# Voltmeter.net
KiCad netlist of a schematic drawn in EAGLE
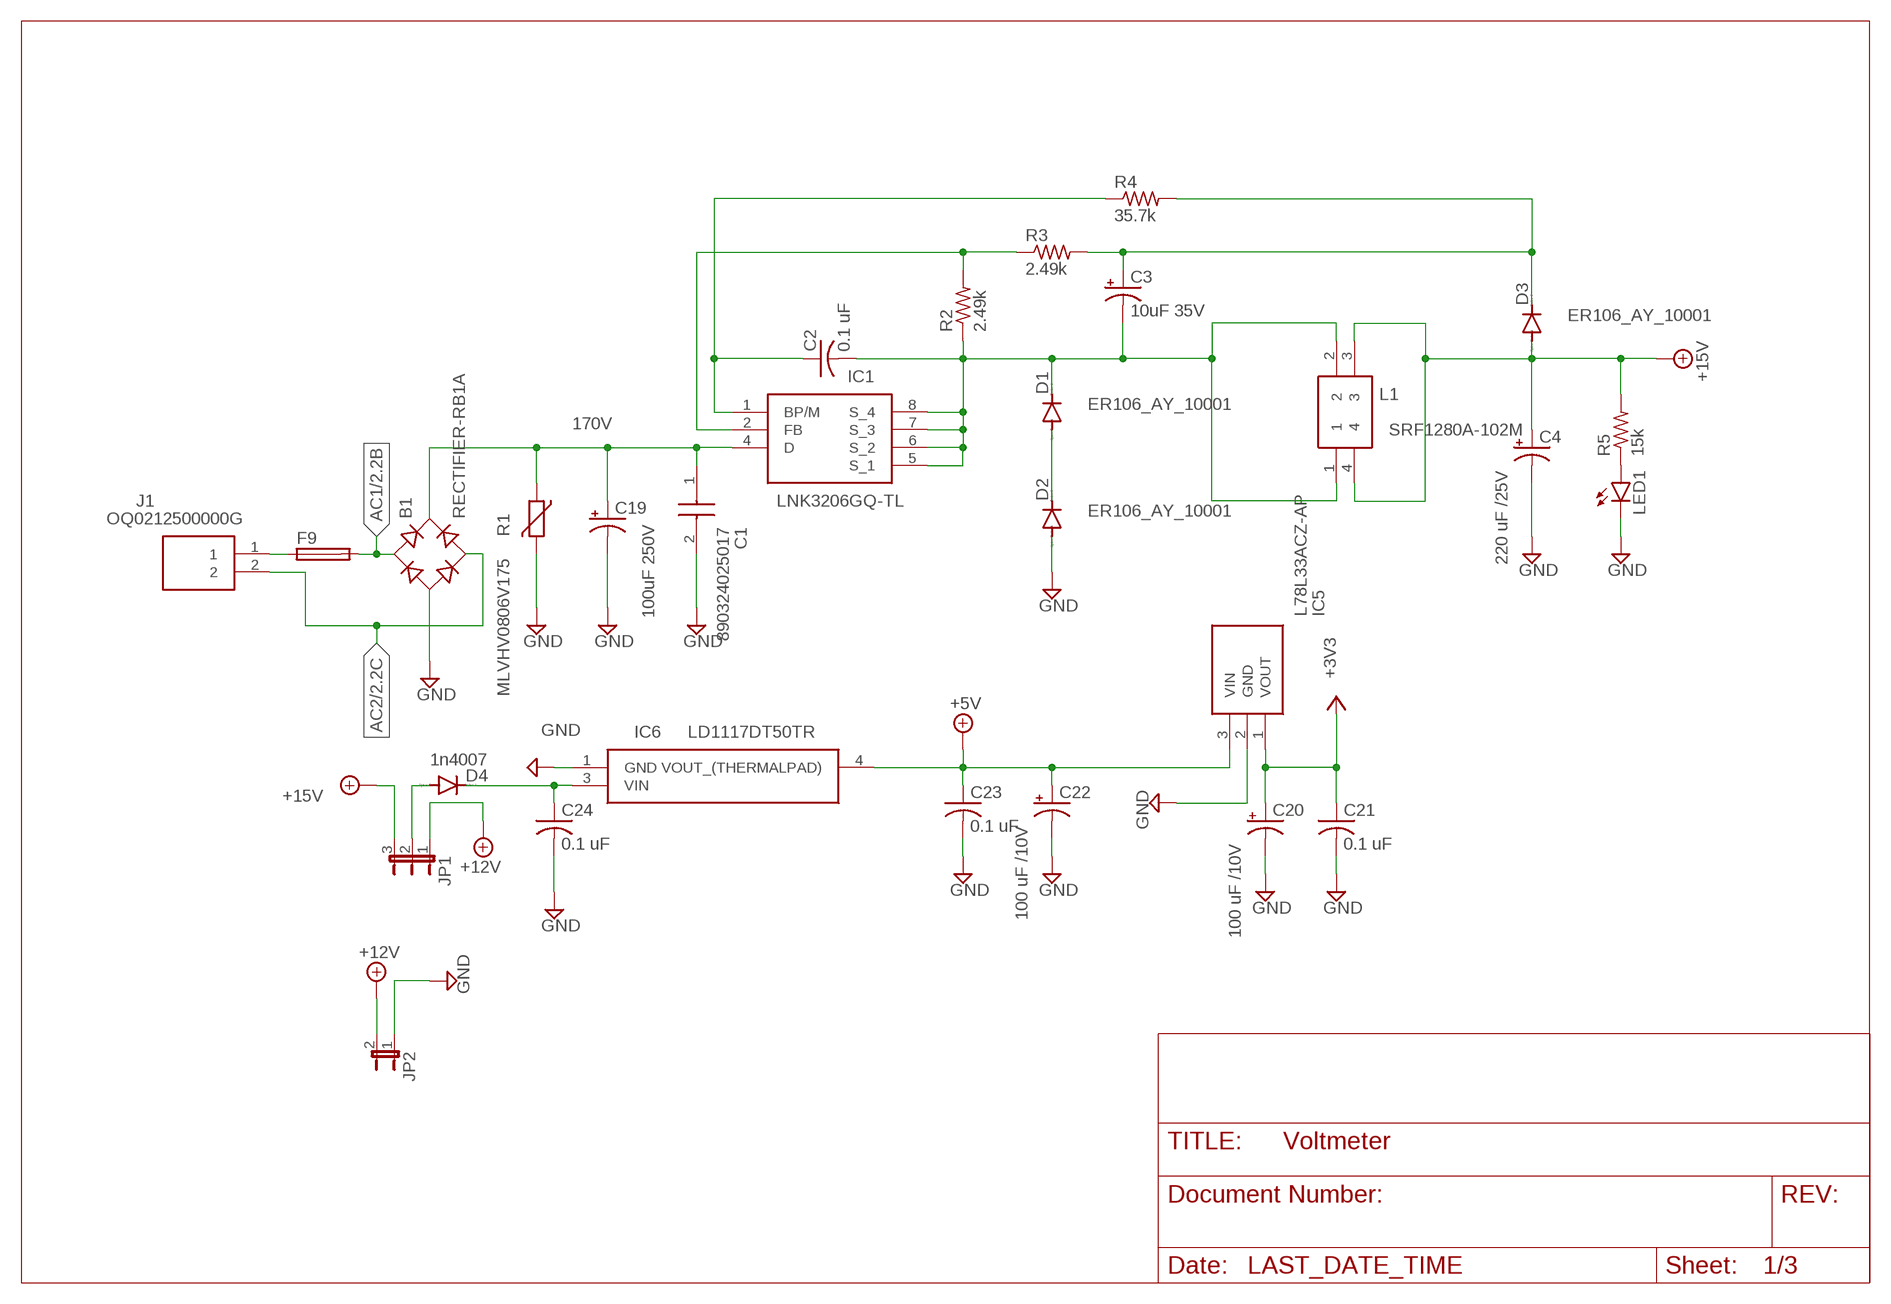
[diagram p0: schematic, sheet 1]
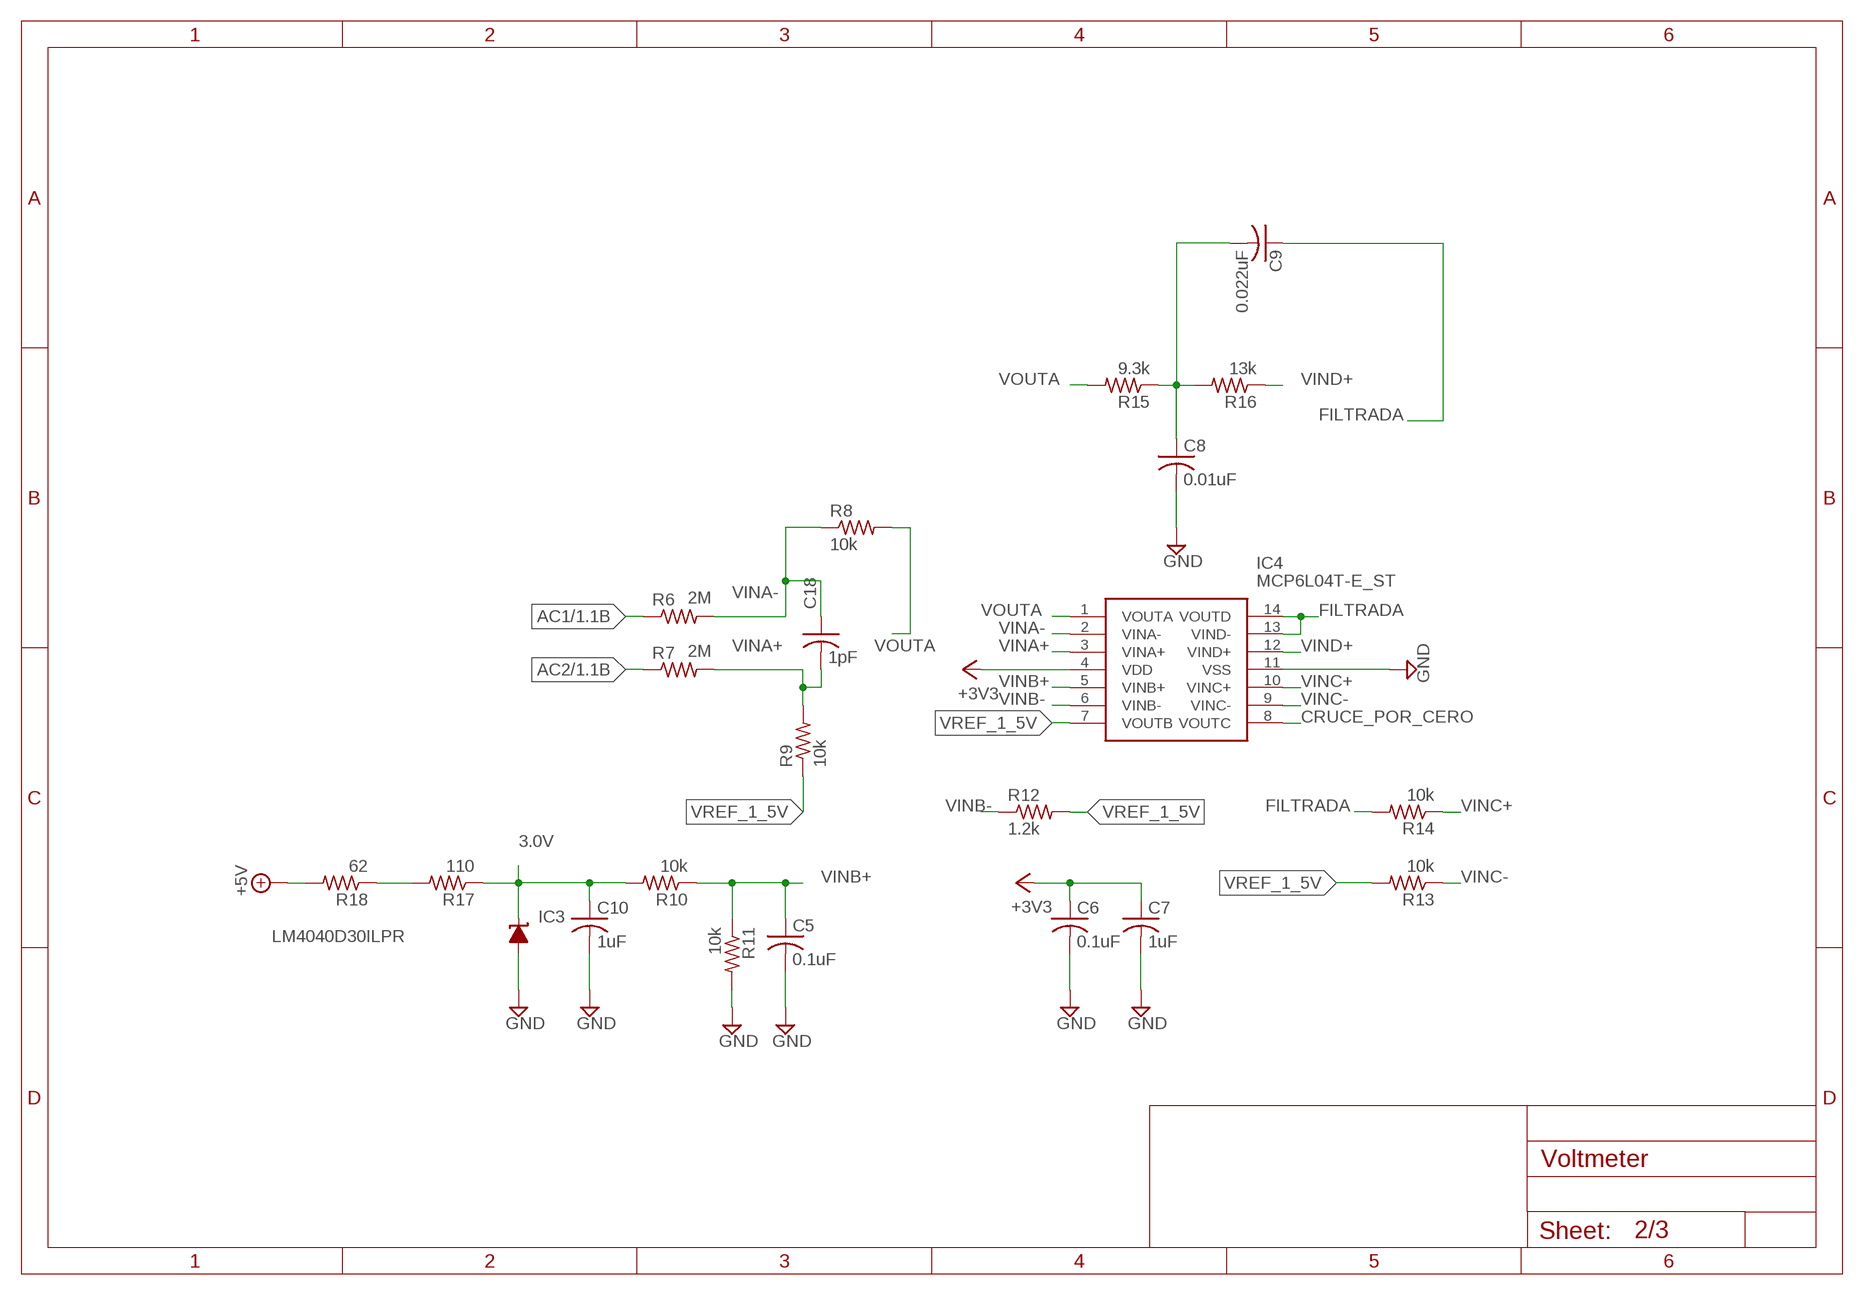
[diagram p1: schematic, sheet 2]
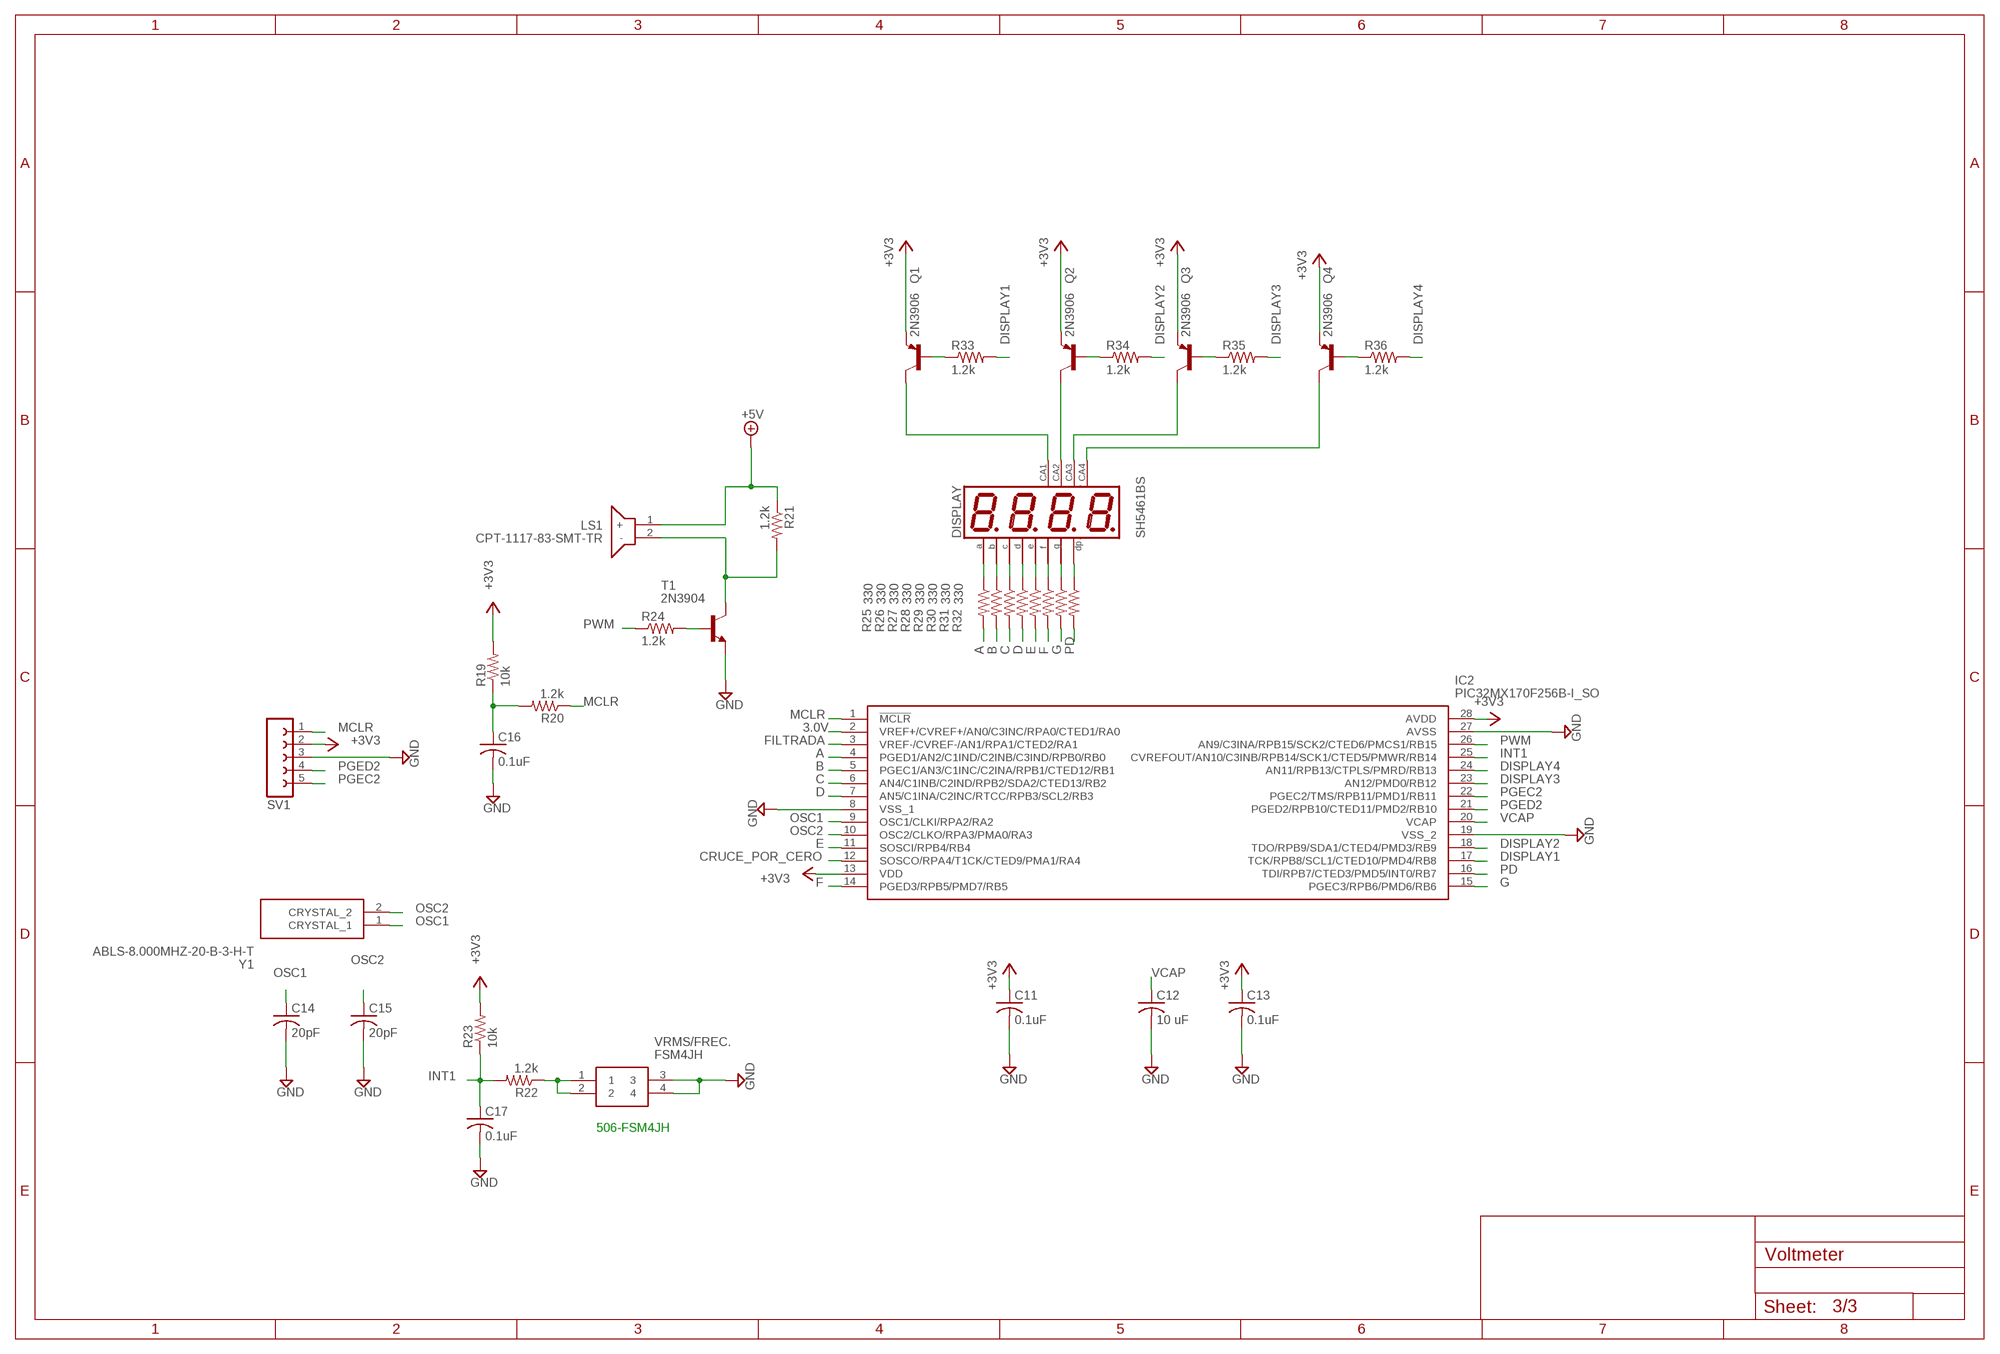
[diagram p2: schematic, sheet 3]

(export (version "E")
  (design (tool "Eeschema 10.0.6"))
  (components
    (comp (ref "C11")
      (value "0.1uF")
      (footprint "eagle-import:C0603K")
      (libsource (lib "eagle-import") (part "C-USC0603K"))
    )
    (comp (ref "C12")
      (value "10 uF")
      (footprint "eagle-import:C1206")
      (libsource (lib "eagle-import") (part "C-USC1206"))
    )
    (comp (ref "C13")
      (value "0.1uF")
      (footprint "eagle-import:C0603K")
      (libsource (lib "eagle-import") (part "C-USC0603K"))
    )
    (comp (ref "C14")
      (value "20pF")
      (footprint "eagle-import:C0603K")
      (libsource (lib "eagle-import") (part "C-USC0603K"))
    )
    (comp (ref "C15")
      (value "20pF")
      (footprint "eagle-import:C0603K")
      (libsource (lib "eagle-import") (part "C-USC0603K"))
    )
    (comp (ref "C16")
      (value "0.1uF")
      (footprint "eagle-import:C0603K")
      (libsource (lib "eagle-import") (part "C-USC0603K"))
    )
    (comp (ref "C17")
      (value "0.1uF")
      (footprint "eagle-import:C0603K")
      (libsource (lib "eagle-import") (part "C-USC0603K"))
    )
    (comp (ref "DISPLAY")
      (value "SH5461BS")
      (footprint "eagle-import:BX56_FR3")
      (libsource (lib "eagle-import") (part "SH5461BS"))
    )
    (comp (ref "IC2")
      (value "PIC32MX170F256B-I_SO")
      (footprint "eagle-import:SOIC127P1030X265-28N")
      (fields
        (field (name "MANUFACTURER_PART_NUMBER") "PIC32MX170F256B-I/SO")
        (field (name "MOUSER_PART_NUMBER") "579-32MX170F256BI/SO")
      )
      (libsource (lib "eagle-import") (part "PIC32MX170F256B-I_SO"))
    )
    (comp (ref "LS1")
      (value "CPT-1117-83-SMT-TR")
      (footprint "eagle-import:CPT111783SMTTR")
      (fields (field (name "MOUSER_PART_NUMBER") "490-CPT-1117-83SMTTR"))
      (libsource (lib "eagle-import") (part "CPT-1117-83-SMT-TR"))
    )
    (comp (ref "Q1")
      (value "2N3906")
      (footprint "eagle-import:TO92")
      (libsource (lib "eagle-import") (part "2N3906"))
    )
    (comp (ref "Q2")
      (value "2N3906")
      (footprint "eagle-import:TO92")
      (libsource (lib "eagle-import") (part "2N3906"))
    )
    (comp (ref "Q3")
      (value "2N3906")
      (footprint "eagle-import:TO92")
      (libsource (lib "eagle-import") (part "2N3906"))
    )
    (comp (ref "Q4")
      (value "2N3906")
      (footprint "eagle-import:TO92")
      (libsource (lib "eagle-import") (part "2N3906"))
    )
    (comp (ref "R19")
      (value "10k")
      (footprint "eagle-import:R0603")
      (libsource (lib "eagle-import") (part "R-US_R0603"))
    )
    (comp (ref "R20")
      (value "1.2k")
      (footprint "eagle-import:R0603")
      (libsource (lib "eagle-import") (part "R-US_R0603"))
    )
    (comp (ref "R21")
      (value "1.2k")
      (footprint "eagle-import:R0603")
      (libsource (lib "eagle-import") (part "R-US_R0603"))
    )
    (comp (ref "R22")
      (value "1.2k")
      (footprint "eagle-import:R0603")
      (libsource (lib "eagle-import") (part "R-US_R0603"))
    )
    (comp (ref "R23")
      (value "10k")
      (footprint "eagle-import:R0603")
      (libsource (lib "eagle-import") (part "R-US_R0603"))
    )
    (comp (ref "R24")
      (value "1.2k")
      (footprint "eagle-import:R0603")
      (libsource (lib "eagle-import") (part "R-US_R0603"))
    )
    (comp (ref "R25")
      (value "330")
      (footprint "eagle-import:R0603")
      (libsource (lib "eagle-import") (part "R-US_R0603"))
    )
    (comp (ref "R26")
      (value "330")
      (footprint "eagle-import:R0603")
      (libsource (lib "eagle-import") (part "R-US_R0603"))
    )
    (comp (ref "R27")
      (value "330")
      (footprint "eagle-import:R0603")
      (libsource (lib "eagle-import") (part "R-US_R0603"))
    )
    (comp (ref "R28")
      (value "330")
      (footprint "eagle-import:R0603")
      (libsource (lib "eagle-import") (part "R-US_R0603"))
    )
    (comp (ref "R29")
      (value "330")
      (footprint "eagle-import:R0603")
      (libsource (lib "eagle-import") (part "R-US_R0603"))
    )
    (comp (ref "R30")
      (value "330")
      (footprint "eagle-import:R0603")
      (libsource (lib "eagle-import") (part "R-US_R0603"))
    )
    (comp (ref "R31")
      (value "330")
      (footprint "eagle-import:R0603")
      (libsource (lib "eagle-import") (part "R-US_R0603"))
    )
    (comp (ref "R32")
      (value "330")
      (footprint "eagle-import:R0603")
      (libsource (lib "eagle-import") (part "R-US_R0603"))
    )
    (comp (ref "R33")
      (value "1.2k")
      (footprint "eagle-import:R0603")
      (libsource (lib "eagle-import") (part "R-US_R0603"))
    )
    (comp (ref "R34")
      (value "1.2k")
      (footprint "eagle-import:R0603")
      (libsource (lib "eagle-import") (part "R-US_R0603"))
    )
    (comp (ref "R35")
      (value "1.2k")
      (footprint "eagle-import:R0603")
      (libsource (lib "eagle-import") (part "R-US_R0603"))
    )
    (comp (ref "R36")
      (value "1.2k")
      (footprint "eagle-import:R0603")
      (libsource (lib "eagle-import") (part "R-US_R0603"))
    )
    (comp (ref "SV1")
      (value "FE05-1")
      (footprint "eagle-import:FE05-1")
      (libsource (lib "eagle-import") (part "FE05-1"))
    )
    (comp (ref "T1")
      (value "2N3904")
      (footprint "eagle-import:TO92")
      (libsource (lib "eagle-import") (part "2N3904"))
    )
    (comp (ref "VRMS/FREC.")
      (value "FSM4JH")
      (footprint "eagle-import:FSM4JH")
      (fields (field (name "MOUSER_PART_NUMBER") "506-FSM4JH"))
      (libsource (lib "eagle-import") (part "FSM4JH"))
    )
    (comp (ref "Y1")
      (value "ABLS-8.000MHZ-20-B-3-H-T")
      (footprint "eagle-import:ABLS8000MHZ20B3HT")
      (fields
        (field (name "MANUFACTURER_PART_NUMBER") "ABLS-8.000MHz-20-B-3-H-T")
        (field (name "MOUSER_PART_NUMBER") "815-LS8000MHZ20B3HT")
      )
      (libsource (lib "eagle-import") (part "ABLS-8.000MHZ-20-B-3-H-T"))
    )
    (comp (ref "B1")
      (value "RECTIFIER-RB1A")
      (footprint "eagle-import:RB1A")
      (libsource (lib "eagle-import") (part "RECTIFIER-RB1A"))
    )
    (comp (ref "C1")
      (value "890324025017")
      (footprint "eagle-import:890324025017")
      (fields (field (name "MOUSER_PART_NUMBER") "710-890324025017"))
      (libsource (lib "eagle-import") (part "890324025017"))
    )
    (comp (ref "C2")
      (value "0.1 uF")
      (footprint "eagle-import:C0603K")
      (libsource (lib "eagle-import") (part "C-USC0603K"))
    )
    (comp (ref "C3")
      (value "10uF 35V")
      (footprint "eagle-import:E2,5-6")
      (libsource (lib "eagle-import") (part "CPOL-USE2.5-6"))
    )
    (comp (ref "C4")
      (value "220 uF /25V")
      (footprint "eagle-import:E3,5-8")
      (libsource (lib "eagle-import") (part "CPOL-USE3.5-8"))
    )
    (comp (ref "C19")
      (value "100uF 250V")
      (footprint "eagle-import:E5-10,5")
      (libsource (lib "eagle-import") (part "CPOL-USE5-10.5"))
    )
    (comp (ref "C20")
      (value "100 uF /10V")
      (footprint "eagle-import:E2-5")
      (libsource (lib "eagle-import") (part "CPOL-USE2-5"))
    )
    (comp (ref "C21")
      (value "0.1 uF")
      (footprint "eagle-import:C0603K")
      (libsource (lib "eagle-import") (part "C-USC0603K"))
    )
    (comp (ref "C22")
      (value "100 uF /10V")
      (footprint "eagle-import:E2-5")
      (libsource (lib "eagle-import") (part "CPOL-USE2-5"))
    )
    (comp (ref "C23")
      (value "0.1 uF")
      (footprint "eagle-import:C0603K")
      (libsource (lib "eagle-import") (part "C-USC0603K"))
    )
    (comp (ref "C24")
      (value "0.1 uF")
      (footprint "eagle-import:C0603K")
      (libsource (lib "eagle-import") (part "C-USC0603K"))
    )
    (comp (ref "D1")
      (value "ER106_AY_10001")
      (footprint "eagle-import:DO41-7.6")
      (libsource (lib "eagle-import") (part "DIODE-DO41-7.6"))
    )
    (comp (ref "D2")
      (value "ER106_AY_10001")
      (footprint "eagle-import:DO41-7.6")
      (libsource (lib "eagle-import") (part "DIODE-DO41-7.6"))
    )
    (comp (ref "D3")
      (value "ER106_AY_10001")
      (footprint "eagle-import:DO41-7.6")
      (libsource (lib "eagle-import") (part "DIODE-DO41-7.6"))
    )
    (comp (ref "D4")
      (value "1n4007")
      (footprint "eagle-import:DO41-7.6")
      (libsource (lib "eagle-import") (part "DIODE-DO41-7.6"))
    )
    (comp (ref "F9")
      (value "LITTLEFUSE")
      (footprint "eagle-import:LITTLEFUSE")
      (libsource (lib "eagle-import") (part "LITTLEFUSE"))
    )
    (comp (ref "IC1")
      (value "LNK3206GQ-TL")
      (footprint "eagle-import:TOP253GNTL")
      (fields (field (name "MOUSER_PART_NUMBER") "869-LNK3206GQ-TL"))
      (libsource (lib "eagle-import") (part "LNK3206GQ-TL"))
    )
    (comp (ref "IC5")
      (value "L78L33ACZ-AP")
      (footprint "eagle-import:TS1107A1AP")
      (fields (field (name "MOUSER_PART_NUMBER") "511-L78L33ACZ-AP"))
      (libsource (lib "eagle-import") (part "L78L33ACZ-AP"))
    )
    (comp (ref "IC6")
      (value "LD1117DT50TR")
      (footprint "eagle-import:TO228P972X240-3N")
      (fields (field (name "MOUSER_PART_NUMBER") "511-LD1117DT50-TR"))
      (libsource (lib "eagle-import") (part "LD1117DT50TR"))
    )
    (comp (ref "J1")
      (value "OQ0212500000G")
      (footprint "eagle-import:OQ0212500000G")
      (fields (field (name "MOUSER_PART_NUMBER") "649-220107-C021A01LF"))
      (libsource (lib "eagle-import") (part "OQ0212500000G"))
    )
    (comp (ref "JP1")
      (value "JP2E")
      (footprint "eagle-import:JP2")
      (libsource (lib "eagle-import") (part "JP2E"))
    )
    (comp (ref "JP2")
      (value "JP1E")
      (footprint "eagle-import:JP1")
      (libsource (lib "eagle-import") (part "JP1E"))
    )
    (comp (ref "L1")
      (value "SRF1280A-102M")
      (footprint "eagle-import:SRF1280A102M")
      (fields (field (name "MOUSER_PART_NUMBER") "652-SRF1280A-102M"))
      (libsource (lib "eagle-import") (part "SRF1280A-102M"))
    )
    (comp (ref "LED1")
      (value "LEDSML0805")
      (footprint "eagle-import:SML0805")
      (libsource (lib "eagle-import") (part "LEDSML0805"))
    )
    (comp (ref "R1")
      (value "MLVHV0806V175")
      (footprint "eagle-import:CT_CN1206")
      (libsource (lib "eagle-import") (part "VARISTORCN1206"))
    )
    (comp (ref "R2")
      (value "2.49k")
      (footprint "eagle-import:R0603")
      (libsource (lib "eagle-import") (part "R-US_R0603"))
    )
    (comp (ref "R3")
      (value "2.49k")
      (footprint "eagle-import:R0603")
      (libsource (lib "eagle-import") (part "R-US_R0603"))
    )
    (comp (ref "R4")
      (value "35.7k")
      (footprint "eagle-import:R0805")
      (libsource (lib "eagle-import") (part "R-US_R0805"))
    )
    (comp (ref "R5")
      (value "15k")
      (footprint "eagle-import:R0603")
      (libsource (lib "eagle-import") (part "R-US_R0603"))
    )
    (comp (ref "C5")
      (value "0.1uF")
      (footprint "eagle-import:C0603K")
      (libsource (lib "eagle-import") (part "C-USC0603K"))
    )
    (comp (ref "C6")
      (value "0.1uF")
      (footprint "eagle-import:C0603K")
      (libsource (lib "eagle-import") (part "C-USC0603K"))
    )
    (comp (ref "C7")
      (value "1uF")
      (footprint "eagle-import:C0603K")
      (libsource (lib "eagle-import") (part "C-USC0603K"))
    )
    (comp (ref "C8")
      (value "0.01uF")
      (footprint "eagle-import:C0603K")
      (libsource (lib "eagle-import") (part "C-USC0603K"))
    )
    (comp (ref "C9")
      (value "0.022uF")
      (footprint "eagle-import:C0603K")
      (libsource (lib "eagle-import") (part "C-USC0603K"))
    )
    (comp (ref "C10")
      (value "1uF")
      (footprint "eagle-import:C0603K")
      (libsource (lib "eagle-import") (part "C-USC0603K"))
    )
    (comp (ref "C18")
      (value "1pF")
      (footprint "eagle-import:C0603K")
      (libsource (lib "eagle-import") (part "C-USC0603K"))
    )
    (comp (ref "IC3")
      (value "LM4040D30ILPR")
      (footprint "eagle-import:LP_O-PBCY-W3")
      (libsource (lib "eagle-import") (part "LM4041LPA12"))
    )
    (comp (ref "IC4")
      (value "MCP6L04T-E_ST")
      (footprint "eagle-import:SOP65P640X120-14N")
      (fields
        (field (name "MANUFACTURER_PART_NUMBER") "MCP6L04T-E/ST")
        (field (name "MOUSER_PART_NUMBER") "579-MCP6L04T-E/ST")
      )
      (libsource (lib "eagle-import") (part "MCP6L04T-E_ST"))
    )
    (comp (ref "R6")
      (value "2M")
      (footprint "eagle-import:R0603")
      (libsource (lib "eagle-import") (part "R-US_R0603"))
    )
    (comp (ref "R7")
      (value "2M")
      (footprint "eagle-import:R0603")
      (libsource (lib "eagle-import") (part "R-US_R0603"))
    )
    (comp (ref "R8")
      (value "10k")
      (footprint "eagle-import:R0603")
      (libsource (lib "eagle-import") (part "R-US_R0603"))
    )
    (comp (ref "R9")
      (value "10k")
      (footprint "eagle-import:R0603")
      (libsource (lib "eagle-import") (part "R-US_R0603"))
    )
    (comp (ref "R10")
      (value "10k")
      (footprint "eagle-import:R0603")
      (libsource (lib "eagle-import") (part "R-US_R0603"))
    )
    (comp (ref "R11")
      (value "10k")
      (footprint "eagle-import:R0603")
      (libsource (lib "eagle-import") (part "R-US_R0603"))
    )
    (comp (ref "R12")
      (value "1.2k")
      (footprint "eagle-import:R0603")
      (libsource (lib "eagle-import") (part "R-US_R0603"))
    )
    (comp (ref "R13")
      (value "10k")
      (footprint "eagle-import:R0603")
      (libsource (lib "eagle-import") (part "R-US_R0603"))
    )
    (comp (ref "R14")
      (value "10k")
      (footprint "eagle-import:R0603")
      (libsource (lib "eagle-import") (part "R-US_R0603"))
    )
    (comp (ref "R15")
      (value "9.3k")
      (footprint "eagle-import:R0603")
      (libsource (lib "eagle-import") (part "R-US_R0603"))
    )
    (comp (ref "R16")
      (value "13k")
      (footprint "eagle-import:R0603")
      (libsource (lib "eagle-import") (part "R-US_R0603"))
    )
    (comp (ref "R17")
      (value "110")
      (footprint "eagle-import:R0603")
      (libsource (lib "eagle-import") (part "R-US_R0603"))
    )
    (comp (ref "R18")
      (value "62")
      (footprint "eagle-import:R0603")
      (libsource (lib "eagle-import") (part "R-US_R0603"))
    )
  )
  (nets
    (net (code "1") (name "+3V3") (class "Default")
      (node (ref "C11") (pin "1") (pinfunction "1_1") (pintype "passive"))
      (node (ref "C13") (pin "1") (pinfunction "1_1") (pintype "passive"))
      (node (ref "C20") (pin "+") (pinfunction "+_+") (pintype "passive"))
      (node (ref "C21") (pin "1") (pinfunction "1_1") (pintype "passive"))
      (node (ref "C6") (pin "1") (pinfunction "1_1") (pintype "passive"))
      (node (ref "C7") (pin "1") (pinfunction "1_1") (pintype "passive"))
      (node (ref "IC2") (pin "13") (pinfunction "VDD_13") (pintype "bidirectional"))
      (node (ref "IC2") (pin "28") (pinfunction "AVDD_28") (pintype "bidirectional"))
      (node (ref "IC4") (pin "4") (pinfunction "VDD_4") (pintype "bidirectional"))
      (node (ref "IC5") (pin "1") (pinfunction "VOUT_1") (pintype "bidirectional"))
      (node (ref "Q1") (pin "3") (pinfunction "E_3") (pintype "passive"))
      (node (ref "Q2") (pin "3") (pinfunction "E_3") (pintype "passive"))
      (node (ref "Q3") (pin "3") (pinfunction "E_3") (pintype "passive"))
      (node (ref "Q4") (pin "3") (pinfunction "E_3") (pintype "passive"))
      (node (ref "R19") (pin "2") (pinfunction "2_2") (pintype "passive"))
      (node (ref "R23") (pin "2") (pinfunction "2_2") (pintype "passive"))
      (node (ref "SV1") (pin "2") (pinfunction "2_2") (pintype "passive"))
    )
    (net (code "2") (name "+5V") (class "Default")
      (node (ref "C22") (pin "+") (pinfunction "+_+") (pintype "passive"))
      (node (ref "C23") (pin "1") (pinfunction "1_1") (pintype "passive"))
      (node (ref "IC5") (pin "3") (pinfunction "VIN_3") (pintype "bidirectional"))
      (node (ref "IC6") (pin "4") (pinfunction "VOUT_(THERMALPAD)_4") (pintype "output"))
      (node (ref "LS1") (pin "1") (pinfunction "+_1") (pintype "bidirectional"))
      (node (ref "R18") (pin "2") (pinfunction "2_2") (pintype "passive"))
      (node (ref "R21") (pin "1") (pinfunction "1_1") (pintype "passive"))
    )
    (net (code "3") (name "+12V") (class "Default")
      (node (ref "JP1") (pin "1") (pinfunction "1_1") (pintype "passive"))
      (node (ref "JP2") (pin "2") (pinfunction "2_2") (pintype "passive"))
    )
    (net (code "4") (name "+15V") (class "Default")
      (node (ref "C4") (pin "+") (pinfunction "+_+") (pintype "passive"))
      (node (ref "D3") (pin "A") (pinfunction "A_A") (pintype "passive"))
      (node (ref "JP1") (pin "3") (pinfunction "3_3") (pintype "passive"))
      (node (ref "L1") (pin "3") (pinfunction "3_3") (pintype "bidirectional"))
      (node (ref "L1") (pin "4") (pinfunction "4_4") (pintype "bidirectional"))
      (node (ref "R5") (pin "2") (pinfunction "2_2") (pintype "passive"))
    )
    (net (code "5") (name "3.0V") (class "Default")
      (node (ref "C10") (pin "1") (pinfunction "1_1") (pintype "passive"))
      (node (ref "IC2") (pin "2") (pinfunction "VREF+/CVREF+/AN0/C3INC/RPA0/CTED1/RA0_2") (pintype "bidirectional"))
      (node (ref "IC3") (pin "2") (pinfunction "C_2") (pintype "passive"))
      (node (ref "R10") (pin "2") (pinfunction "2_2") (pintype "passive"))
      (node (ref "R17") (pin "1") (pinfunction "1_1") (pintype "passive"))
    )
    (net (code "6") (name "170V") (class "Default")
      (node (ref "B1") (pin "+") (pinfunction "+_+") (pintype "passive"))
      (node (ref "C1") (pin "1") (pinfunction "1_1") (pintype "bidirectional"))
      (node (ref "C19") (pin "+") (pinfunction "+_+") (pintype "passive"))
      (node (ref "IC1") (pin "4") (pinfunction "D_4") (pintype "bidirectional"))
      (node (ref "R1") (pin "1") (pinfunction "1_1") (pintype "passive"))
    )
    (net (code "7") (name "A") (class "Default")
      (node (ref "IC2") (pin "4") (pinfunction "PGED1/AN2/C1IND/C2INB/C3IND/RPB0/RB0_4") (pintype "bidirectional"))
      (node (ref "R25") (pin "2") (pinfunction "2_2") (pintype "passive"))
    )
    (net (code "8") (name "AC1") (class "Default")
      (node (ref "B1") (pin "AC1") (pinfunction "AC1_AC1") (pintype "passive"))
      (node (ref "F9") (pin "2") (pinfunction "2_2") (pintype "passive"))
      (node (ref "R6") (pin "1") (pinfunction "1_1") (pintype "passive"))
    )
    (net (code "9") (name "AC2") (class "Default")
      (node (ref "B1") (pin "AC2") (pinfunction "AC2_AC2") (pintype "passive"))
      (node (ref "J1") (pin "2") (pinfunction "2_2") (pintype "bidirectional"))
      (node (ref "R7") (pin "1") (pinfunction "1_1") (pintype "passive"))
    )
    (net (code "10") (name "B") (class "Default")
      (node (ref "IC2") (pin "5") (pinfunction "PGEC1/AN3/C1INC/C2INA/RPB1/CTED12/RB1_5") (pintype "bidirectional"))
      (node (ref "R26") (pin "2") (pinfunction "2_2") (pintype "passive"))
    )
    (net (code "11") (name "C") (class "Default")
      (node (ref "IC2") (pin "6") (pinfunction "AN4/C1INB/C2IND/RPB2/SDA2/CTED13/RB2_6") (pintype "bidirectional"))
      (node (ref "R27") (pin "2") (pinfunction "2_2") (pintype "passive"))
    )
    (net (code "12") (name "CRUCE_POR_CERO") (class "Default")
      (node (ref "IC2") (pin "12") (pinfunction "SOSCO/RPA4/T1CK/CTED9/PMA1/RA4_12") (pintype "bidirectional"))
      (node (ref "IC4") (pin "8") (pinfunction "VOUTC_8") (pintype "bidirectional"))
    )
    (net (code "13") (name "D") (class "Default")
      (node (ref "IC2") (pin "7") (pinfunction "AN5/C1INA/C2INC/RTCC/RPB3/SCL2/RB3_7") (pintype "bidirectional"))
      (node (ref "R28") (pin "2") (pinfunction "2_2") (pintype "passive"))
    )
    (net (code "14") (name "DISPLAY1") (class "Default")
      (node (ref "IC2") (pin "17") (pinfunction "TCK/RPB8/SCL1/CTED10/PMD4/RB8_17") (pintype "bidirectional"))
      (node (ref "R33") (pin "2") (pinfunction "2_2") (pintype "passive"))
    )
    (net (code "15") (name "DISPLAY2") (class "Default")
      (node (ref "IC2") (pin "18") (pinfunction "TDO/RPB9/SDA1/CTED4/PMD3/RB9_18") (pintype "bidirectional"))
      (node (ref "R34") (pin "2") (pinfunction "2_2") (pintype "passive"))
    )
    (net (code "16") (name "DISPLAY3") (class "Default")
      (node (ref "IC2") (pin "23") (pinfunction "AN12/PMD0/RB12_23") (pintype "bidirectional"))
      (node (ref "R35") (pin "2") (pinfunction "2_2") (pintype "passive"))
    )
    (net (code "17") (name "DISPLAY4") (class "Default")
      (node (ref "IC2") (pin "24") (pinfunction "AN11/RPB13/CTPLS/PMRD/RB13_24") (pintype "bidirectional"))
      (node (ref "R36") (pin "2") (pinfunction "2_2") (pintype "passive"))
    )
    (net (code "18") (name "E") (class "Default")
      (node (ref "IC2") (pin "11") (pinfunction "SOSCI/RPB4/RB4_11") (pintype "bidirectional"))
      (node (ref "R29") (pin "2") (pinfunction "2_2") (pintype "passive"))
    )
    (net (code "19") (name "F") (class "Default")
      (node (ref "IC2") (pin "14") (pinfunction "PGED3/RPB5/PMD7/RB5_14") (pintype "bidirectional"))
      (node (ref "R30") (pin "2") (pinfunction "2_2") (pintype "passive"))
    )
    (net (code "20") (name "FILTRADA") (class "Default")
      (node (ref "C9") (pin "1") (pinfunction "1_1") (pintype "passive"))
      (node (ref "IC2") (pin "3") (pinfunction "VREF-/CVREF-/AN1/RPA1/CTED2/RA1_3") (pintype "bidirectional"))
      (node (ref "IC4") (pin "13") (pinfunction "VIND-_13") (pintype "bidirectional"))
      (node (ref "IC4") (pin "14") (pinfunction "VOUTD_14") (pintype "bidirectional"))
      (node (ref "R14") (pin "2") (pinfunction "2_2") (pintype "passive"))
    )
    (net (code "21") (name "G") (class "Default")
      (node (ref "IC2") (pin "15") (pinfunction "PGEC3/RPB6/PMD6/RB6_15") (pintype "bidirectional"))
      (node (ref "R31") (pin "2") (pinfunction "2_2") (pintype "passive"))
    )
    (net (code "22") (name "GND") (class "Default")
      (node (ref "B1") (pin "-") (pinfunction "-_-") (pintype "passive"))
      (node (ref "C1") (pin "2") (pinfunction "2_2") (pintype "bidirectional"))
      (node (ref "C10") (pin "2") (pinfunction "2_2") (pintype "passive"))
      (node (ref "C11") (pin "2") (pinfunction "2_2") (pintype "passive"))
      (node (ref "C12") (pin "2") (pinfunction "2_2") (pintype "passive"))
      (node (ref "C13") (pin "2") (pinfunction "2_2") (pintype "passive"))
      (node (ref "C14") (pin "2") (pinfunction "2_2") (pintype "passive"))
      (node (ref "C15") (pin "2") (pinfunction "2_2") (pintype "passive"))
      (node (ref "C16") (pin "2") (pinfunction "2_2") (pintype "passive"))
      (node (ref "C17") (pin "2") (pinfunction "2_2") (pintype "passive"))
      (node (ref "C19") (pin "-") (pinfunction "-_-") (pintype "passive"))
      (node (ref "C20") (pin "-") (pinfunction "-_-") (pintype "passive"))
      (node (ref "C21") (pin "2") (pinfunction "2_2") (pintype "passive"))
      (node (ref "C22") (pin "-") (pinfunction "-_-") (pintype "passive"))
      (node (ref "C23") (pin "2") (pinfunction "2_2") (pintype "passive"))
      (node (ref "C24") (pin "2") (pinfunction "2_2") (pintype "passive"))
      (node (ref "C4") (pin "-") (pinfunction "-_-") (pintype "passive"))
      (node (ref "C5") (pin "2") (pinfunction "2_2") (pintype "passive"))
      (node (ref "C6") (pin "2") (pinfunction "2_2") (pintype "passive"))
      (node (ref "C7") (pin "2") (pinfunction "2_2") (pintype "passive"))
      (node (ref "C8") (pin "2") (pinfunction "2_2") (pintype "passive"))
      (node (ref "D2") (pin "A") (pinfunction "A_A") (pintype "passive"))
      (node (ref "IC2") (pin "19") (pinfunction "VSS_2_19") (pintype "bidirectional"))
      (node (ref "IC2") (pin "27") (pinfunction "AVSS_27") (pintype "bidirectional"))
      (node (ref "IC2") (pin "8") (pinfunction "VSS_1_8") (pintype "bidirectional"))
      (node (ref "IC3") (pin "3") (pinfunction "A_3") (pintype "passive"))
      (node (ref "IC4") (pin "11") (pinfunction "VSS_11") (pintype "bidirectional"))
      (node (ref "IC5") (pin "2") (pinfunction "GND_2") (pintype "bidirectional"))
      (node (ref "IC6") (pin "1") (pinfunction "GND_1") (pintype "input"))
      (node (ref "JP2") (pin "1") (pinfunction "1_1") (pintype "passive"))
      (node (ref "LED1") (pin "C") (pinfunction "C_C") (pintype "passive"))
      (node (ref "R1") (pin "2") (pinfunction "2_2") (pintype "passive"))
      (node (ref "R11") (pin "2") (pinfunction "2_2") (pintype "passive"))
      (node (ref "SV1") (pin "3") (pinfunction "3_3") (pintype "passive"))
      (node (ref "T1") (pin "3") (pinfunction "E_3") (pintype "passive"))
      (node (ref "VRMS/FREC.") (pin "3") (pinfunction "3_3") (pintype "bidirectional"))
      (node (ref "VRMS/FREC.") (pin "4") (pinfunction "4_4") (pintype "bidirectional"))
    )
    (net (code "23") (name "INT1") (class "Default")
      (node (ref "C17") (pin "1") (pinfunction "1_1") (pintype "passive"))
      (node (ref "IC2") (pin "25") (pinfunction "CVREFOUT/AN10/C3INB/RPB14/SCK1/CTED5/PMWR/RB14_25") (pintype "bidirectional"))
      (node (ref "R22") (pin "2") (pinfunction "2_2") (pintype "passive"))
      (node (ref "R23") (pin "1") (pinfunction "1_1") (pintype "passive"))
    )
    (net (code "24") (name "MCLR") (class "Default")
      (node (ref "IC2") (pin "1") (pinfunction "~{MCLR}_1") (pintype "bidirectional"))
      (node (ref "R20") (pin "1") (pinfunction "1_1") (pintype "passive"))
      (node (ref "SV1") (pin "1") (pinfunction "1_1") (pintype "passive"))
    )
    (net (code "25") (name "Net-(C3-Pad+)") (class "Default")
      (node (ref "C3") (pin "+") (pinfunction "+_+") (pintype "passive"))
      (node (ref "D3") (pin "C") (pinfunction "C_C") (pintype "passive"))
      (node (ref "R3") (pin "2") (pinfunction "2_2") (pintype "passive"))
      (node (ref "R4") (pin "2") (pinfunction "2_2") (pintype "passive"))
    )
    (net (code "26") (name "Net-(C8-Pad1)") (class "Default")
      (node (ref "C8") (pin "1") (pinfunction "1_1") (pintype "passive"))
      (node (ref "C9") (pin "2") (pinfunction "2_2") (pintype "passive"))
      (node (ref "R15") (pin "1") (pinfunction "1_1") (pintype "passive"))
      (node (ref "R16") (pin "2") (pinfunction "2_2") (pintype "passive"))
    )
    (net (code "27") (name "Net-(C16-Pad1)") (class "Default")
      (node (ref "C16") (pin "1") (pinfunction "1_1") (pintype "passive"))
      (node (ref "R19") (pin "1") (pinfunction "1_1") (pintype "passive"))
      (node (ref "R20") (pin "2") (pinfunction "2_2") (pintype "passive"))
    )
    (net (code "28") (name "Net-(D1-PadA)") (class "Default")
      (node (ref "D1") (pin "A") (pinfunction "A_A") (pintype "passive"))
      (node (ref "D2") (pin "C") (pinfunction "C_C") (pintype "passive"))
    )
    (net (code "29") (name "Net-(D4-PadA)") (class "Default")
      (node (ref "D4") (pin "A") (pinfunction "A_A") (pintype "passive"))
      (node (ref "JP1") (pin "2") (pinfunction "2_2") (pintype "passive"))
    )
    (net (code "30") (name "Net-(DISPLAY-A)") (class "Default")
      (node (ref "DISPLAY") (pin "11") (pinfunction "A_11") (pintype "passive"))
      (node (ref "R25") (pin "1") (pinfunction "1_1") (pintype "passive"))
    )
    (net (code "31") (name "Net-(DISPLAY-B)") (class "Default")
      (node (ref "DISPLAY") (pin "7") (pinfunction "B_7") (pintype "passive"))
      (node (ref "R26") (pin "1") (pinfunction "1_1") (pintype "passive"))
    )
    (net (code "32") (name "Net-(DISPLAY-C)") (class "Default")
      (node (ref "DISPLAY") (pin "4") (pinfunction "C_4") (pintype "passive"))
      (node (ref "R27") (pin "1") (pinfunction "1_1") (pintype "passive"))
    )
    (net (code "33") (name "Net-(DISPLAY-D)") (class "Default")
      (node (ref "DISPLAY") (pin "2") (pinfunction "D_2") (pintype "passive"))
      (node (ref "R28") (pin "1") (pinfunction "1_1") (pintype "passive"))
    )
    (net (code "34") (name "Net-(DISPLAY-DP)") (class "Default")
      (node (ref "DISPLAY") (pin "3") (pinfunction "DP_3") (pintype "passive"))
      (node (ref "R32") (pin "1") (pinfunction "1_1") (pintype "passive"))
    )
    (net (code "35") (name "Net-(DISPLAY-E)") (class "Default")
      (node (ref "DISPLAY") (pin "1") (pinfunction "E_1") (pintype "passive"))
      (node (ref "R29") (pin "1") (pinfunction "1_1") (pintype "passive"))
    )
    (net (code "36") (name "Net-(DISPLAY-F)") (class "Default")
      (node (ref "DISPLAY") (pin "10") (pinfunction "F_10") (pintype "passive"))
      (node (ref "R30") (pin "1") (pinfunction "1_1") (pintype "passive"))
    )
    (net (code "37") (name "Net-(DISPLAY-G)") (class "Default")
      (node (ref "DISPLAY") (pin "5") (pinfunction "G_5") (pintype "passive"))
      (node (ref "R31") (pin "1") (pinfunction "1_1") (pintype "passive"))
    )
    (net (code "38") (name "Net-(F9-Pad1)") (class "Default")
      (node (ref "F9") (pin "1") (pinfunction "1_1") (pintype "passive"))
      (node (ref "J1") (pin "1") (pinfunction "1_1") (pintype "bidirectional"))
    )
    (net (code "39") (name "Net-(IC1-BP{slash}M)") (class "Default")
      (node (ref "C2") (pin "1") (pinfunction "1_1") (pintype "passive"))
      (node (ref "IC1") (pin "1") (pinfunction "BP/M_1") (pintype "bidirectional"))
      (node (ref "R4") (pin "1") (pinfunction "1_1") (pintype "passive"))
    )
    (net (code "40") (name "Net-(IC1-FB)") (class "Default")
      (node (ref "IC1") (pin "2") (pinfunction "FB_2") (pintype "bidirectional"))
      (node (ref "R2") (pin "2") (pinfunction "2_2") (pintype "passive"))
      (node (ref "R3") (pin "1") (pinfunction "1_1") (pintype "passive"))
    )
    (net (code "41") (name "Net-(IC1-S_1)") (class "Default")
      (node (ref "C2") (pin "2") (pinfunction "2_2") (pintype "passive"))
      (node (ref "C3") (pin "-") (pinfunction "-_-") (pintype "passive"))
      (node (ref "D1") (pin "C") (pinfunction "C_C") (pintype "passive"))
      (node (ref "IC1") (pin "5") (pinfunction "S_1_5") (pintype "bidirectional"))
      (node (ref "IC1") (pin "6") (pinfunction "S_2_6") (pintype "bidirectional"))
      (node (ref "IC1") (pin "7") (pinfunction "S_3_7") (pintype "bidirectional"))
      (node (ref "IC1") (pin "8") (pinfunction "S_4_8") (pintype "bidirectional"))
      (node (ref "L1") (pin "1") (pinfunction "1_1") (pintype "bidirectional"))
      (node (ref "L1") (pin "2") (pinfunction "2_2") (pintype "bidirectional"))
      (node (ref "R2") (pin "1") (pinfunction "1_1") (pintype "passive"))
    )
    (net (code "42") (name "Net-(IC6-VIN)") (class "Default")
      (node (ref "C24") (pin "1") (pinfunction "1_1") (pintype "passive"))
      (node (ref "D4") (pin "C") (pinfunction "C_C") (pintype "passive"))
      (node (ref "IC6") (pin "3") (pinfunction "VIN_3") (pintype "output"))
    )
    (net (code "43") (name "Net-(LED1-PadA)") (class "Default")
      (node (ref "LED1") (pin "A") (pinfunction "A_A") (pintype "passive"))
      (node (ref "R5") (pin "1") (pinfunction "1_1") (pintype "passive"))
    )
    (net (code "44") (name "Net-(LS1--)") (class "Default")
      (node (ref "LS1") (pin "2") (pinfunction "-_2") (pintype "bidirectional"))
      (node (ref "R21") (pin "2") (pinfunction "2_2") (pintype "passive"))
      (node (ref "T1") (pin "1") (pinfunction "C_1") (pintype "passive"))
    )
    (net (code "45") (name "Net-(Q1-B)") (class "Default")
      (node (ref "Q1") (pin "2") (pinfunction "B_2") (pintype "passive"))
      (node (ref "R33") (pin "1") (pinfunction "1_1") (pintype "passive"))
    )
    (net (code "46") (name "Net-(Q1-C)") (class "Default")
      (node (ref "DISPLAY") (pin "12") (pinfunction "CA_12") (pintype "passive"))
      (node (ref "Q1") (pin "1") (pinfunction "C_1") (pintype "passive"))
    )
    (net (code "47") (name "Net-(Q2-B)") (class "Default")
      (node (ref "Q2") (pin "2") (pinfunction "B_2") (pintype "passive"))
      (node (ref "R34") (pin "1") (pinfunction "1_1") (pintype "passive"))
    )
    (net (code "48") (name "Net-(Q2-C)") (class "Default")
      (node (ref "DISPLAY") (pin "9") (pinfunction "CA_9") (pintype "passive"))
      (node (ref "Q2") (pin "1") (pinfunction "C_1") (pintype "passive"))
    )
    (net (code "49") (name "Net-(Q3-B)") (class "Default")
      (node (ref "Q3") (pin "2") (pinfunction "B_2") (pintype "passive"))
      (node (ref "R35") (pin "1") (pinfunction "1_1") (pintype "passive"))
    )
    (net (code "50") (name "Net-(Q3-C)") (class "Default")
      (node (ref "DISPLAY") (pin "8") (pinfunction "CA_8") (pintype "passive"))
      (node (ref "Q3") (pin "1") (pinfunction "C_1") (pintype "passive"))
    )
    (net (code "51") (name "Net-(Q4-B)") (class "Default")
      (node (ref "Q4") (pin "2") (pinfunction "B_2") (pintype "passive"))
      (node (ref "R36") (pin "1") (pinfunction "1_1") (pintype "passive"))
    )
    (net (code "52") (name "Net-(Q4-C)") (class "Default")
      (node (ref "DISPLAY") (pin "6") (pinfunction "CA_6") (pintype "passive"))
      (node (ref "Q4") (pin "1") (pinfunction "C_1") (pintype "passive"))
    )
    (net (code "53") (name "Net-(R17-Pad2)") (class "Default")
      (node (ref "R17") (pin "2") (pinfunction "2_2") (pintype "passive"))
      (node (ref "R18") (pin "1") (pinfunction "1_1") (pintype "passive"))
    )
    (net (code "54") (name "Net-(R22-Pad1)") (class "Default")
      (node (ref "R22") (pin "1") (pinfunction "1_1") (pintype "passive"))
      (node (ref "VRMS/FREC.") (pin "1") (pinfunction "1_1") (pintype "bidirectional"))
      (node (ref "VRMS/FREC.") (pin "2") (pinfunction "2_2") (pintype "bidirectional"))
    )
    (net (code "55") (name "Net-(T1-B)") (class "Default")
      (node (ref "R24") (pin "2") (pinfunction "2_2") (pintype "passive"))
      (node (ref "T1") (pin "2") (pinfunction "B_2") (pintype "passive"))
    )
    (net (code "56") (name "OSC1") (class "Default")
      (node (ref "C14") (pin "1") (pinfunction "1_1") (pintype "passive"))
      (node (ref "IC2") (pin "9") (pinfunction "OSC1/CLKI/RPA2/RA2_9") (pintype "bidirectional"))
      (node (ref "Y1") (pin "1") (pinfunction "CRYSTAL_1_1") (pintype "bidirectional"))
    )
    (net (code "57") (name "OSC2") (class "Default")
      (node (ref "C15") (pin "1") (pinfunction "1_1") (pintype "passive"))
      (node (ref "IC2") (pin "10") (pinfunction "OSC2/CLKO/RPA3/PMA0/RA3_10") (pintype "bidirectional"))
      (node (ref "Y1") (pin "2") (pinfunction "CRYSTAL_2_2") (pintype "bidirectional"))
    )
    (net (code "58") (name "PD") (class "Default")
      (node (ref "IC2") (pin "16") (pinfunction "TDI/RPB7/CTED3/PMD5/INT0/RB7_16") (pintype "bidirectional"))
      (node (ref "R32") (pin "2") (pinfunction "2_2") (pintype "passive"))
    )
    (net (code "59") (name "PGEC2") (class "Default")
      (node (ref "IC2") (pin "22") (pinfunction "PGEC2/TMS/RPB11/PMD1/RB11_22") (pintype "bidirectional"))
      (node (ref "SV1") (pin "5") (pinfunction "5_5") (pintype "passive"))
    )
    (net (code "60") (name "PGED2") (class "Default")
      (node (ref "IC2") (pin "21") (pinfunction "PGED2/RPB10/CTED11/PMD2/RB10_21") (pintype "bidirectional"))
      (node (ref "SV1") (pin "4") (pinfunction "4_4") (pintype "passive"))
    )
    (net (code "61") (name "PWM") (class "Default")
      (node (ref "IC2") (pin "26") (pinfunction "AN9/C3INA/RPB15/SCK2/CTED6/PMCS1/RB15_26") (pintype "bidirectional"))
      (node (ref "R24") (pin "1") (pinfunction "1_1") (pintype "passive"))
    )
    (net (code "62") (name "VCAP") (class "Default")
      (node (ref "C12") (pin "1") (pinfunction "1_1") (pintype "passive"))
      (node (ref "IC2") (pin "20") (pinfunction "VCAP_20") (pintype "bidirectional"))
    )
    (net (code "63") (name "VINA+") (class "Default")
      (node (ref "C18") (pin "2") (pinfunction "2_2") (pintype "passive"))
      (node (ref "IC4") (pin "3") (pinfunction "VINA+_3") (pintype "bidirectional"))
      (node (ref "R7") (pin "2") (pinfunction "2_2") (pintype "passive"))
      (node (ref "R9") (pin "2") (pinfunction "2_2") (pintype "passive"))
    )
    (net (code "64") (name "VINA-") (class "Default")
      (node (ref "C18") (pin "1") (pinfunction "1_1") (pintype "passive"))
      (node (ref "IC4") (pin "2") (pinfunction "VINA-_2") (pintype "bidirectional"))
      (node (ref "R6") (pin "2") (pinfunction "2_2") (pintype "passive"))
      (node (ref "R8") (pin "1") (pinfunction "1_1") (pintype "passive"))
    )
    (net (code "65") (name "VINB+") (class "Default")
      (node (ref "C5") (pin "1") (pinfunction "1_1") (pintype "passive"))
      (node (ref "IC4") (pin "5") (pinfunction "VINB+_5") (pintype "bidirectional"))
      (node (ref "R10") (pin "1") (pinfunction "1_1") (pintype "passive"))
      (node (ref "R11") (pin "1") (pinfunction "1_1") (pintype "passive"))
    )
    (net (code "66") (name "VINB-") (class "Default")
      (node (ref "IC4") (pin "6") (pinfunction "VINB-_6") (pintype "bidirectional"))
      (node (ref "R12") (pin "1") (pinfunction "1_1") (pintype "passive"))
    )
    (net (code "67") (name "VINC+") (class "Default")
      (node (ref "IC4") (pin "10") (pinfunction "VINC+_10") (pintype "bidirectional"))
      (node (ref "R14") (pin "1") (pinfunction "1_1") (pintype "passive"))
    )
    (net (code "68") (name "VINC-") (class "Default")
      (node (ref "IC4") (pin "9") (pinfunction "VINC-_9") (pintype "bidirectional"))
      (node (ref "R13") (pin "1") (pinfunction "1_1") (pintype "passive"))
    )
    (net (code "69") (name "VIND+") (class "Default")
      (node (ref "IC4") (pin "12") (pinfunction "VIND+_12") (pintype "bidirectional"))
      (node (ref "R16") (pin "1") (pinfunction "1_1") (pintype "passive"))
    )
    (net (code "70") (name "VOUTA") (class "Default")
      (node (ref "IC4") (pin "1") (pinfunction "VOUTA_1") (pintype "bidirectional"))
      (node (ref "R15") (pin "2") (pinfunction "2_2") (pintype "passive"))
      (node (ref "R8") (pin "2") (pinfunction "2_2") (pintype "passive"))
    )
    (net (code "71") (name "VREF_1_5V") (class "Default")
      (node (ref "IC4") (pin "7") (pinfunction "VOUTB_7") (pintype "bidirectional"))
      (node (ref "R12") (pin "2") (pinfunction "2_2") (pintype "passive"))
      (node (ref "R13") (pin "2") (pinfunction "2_2") (pintype "passive"))
      (node (ref "R9") (pin "1") (pinfunction "1_1") (pintype "passive"))
    )
  )
)
